# as5600-module.net
KiCad netlist of a schematic drawn in Altium Designer
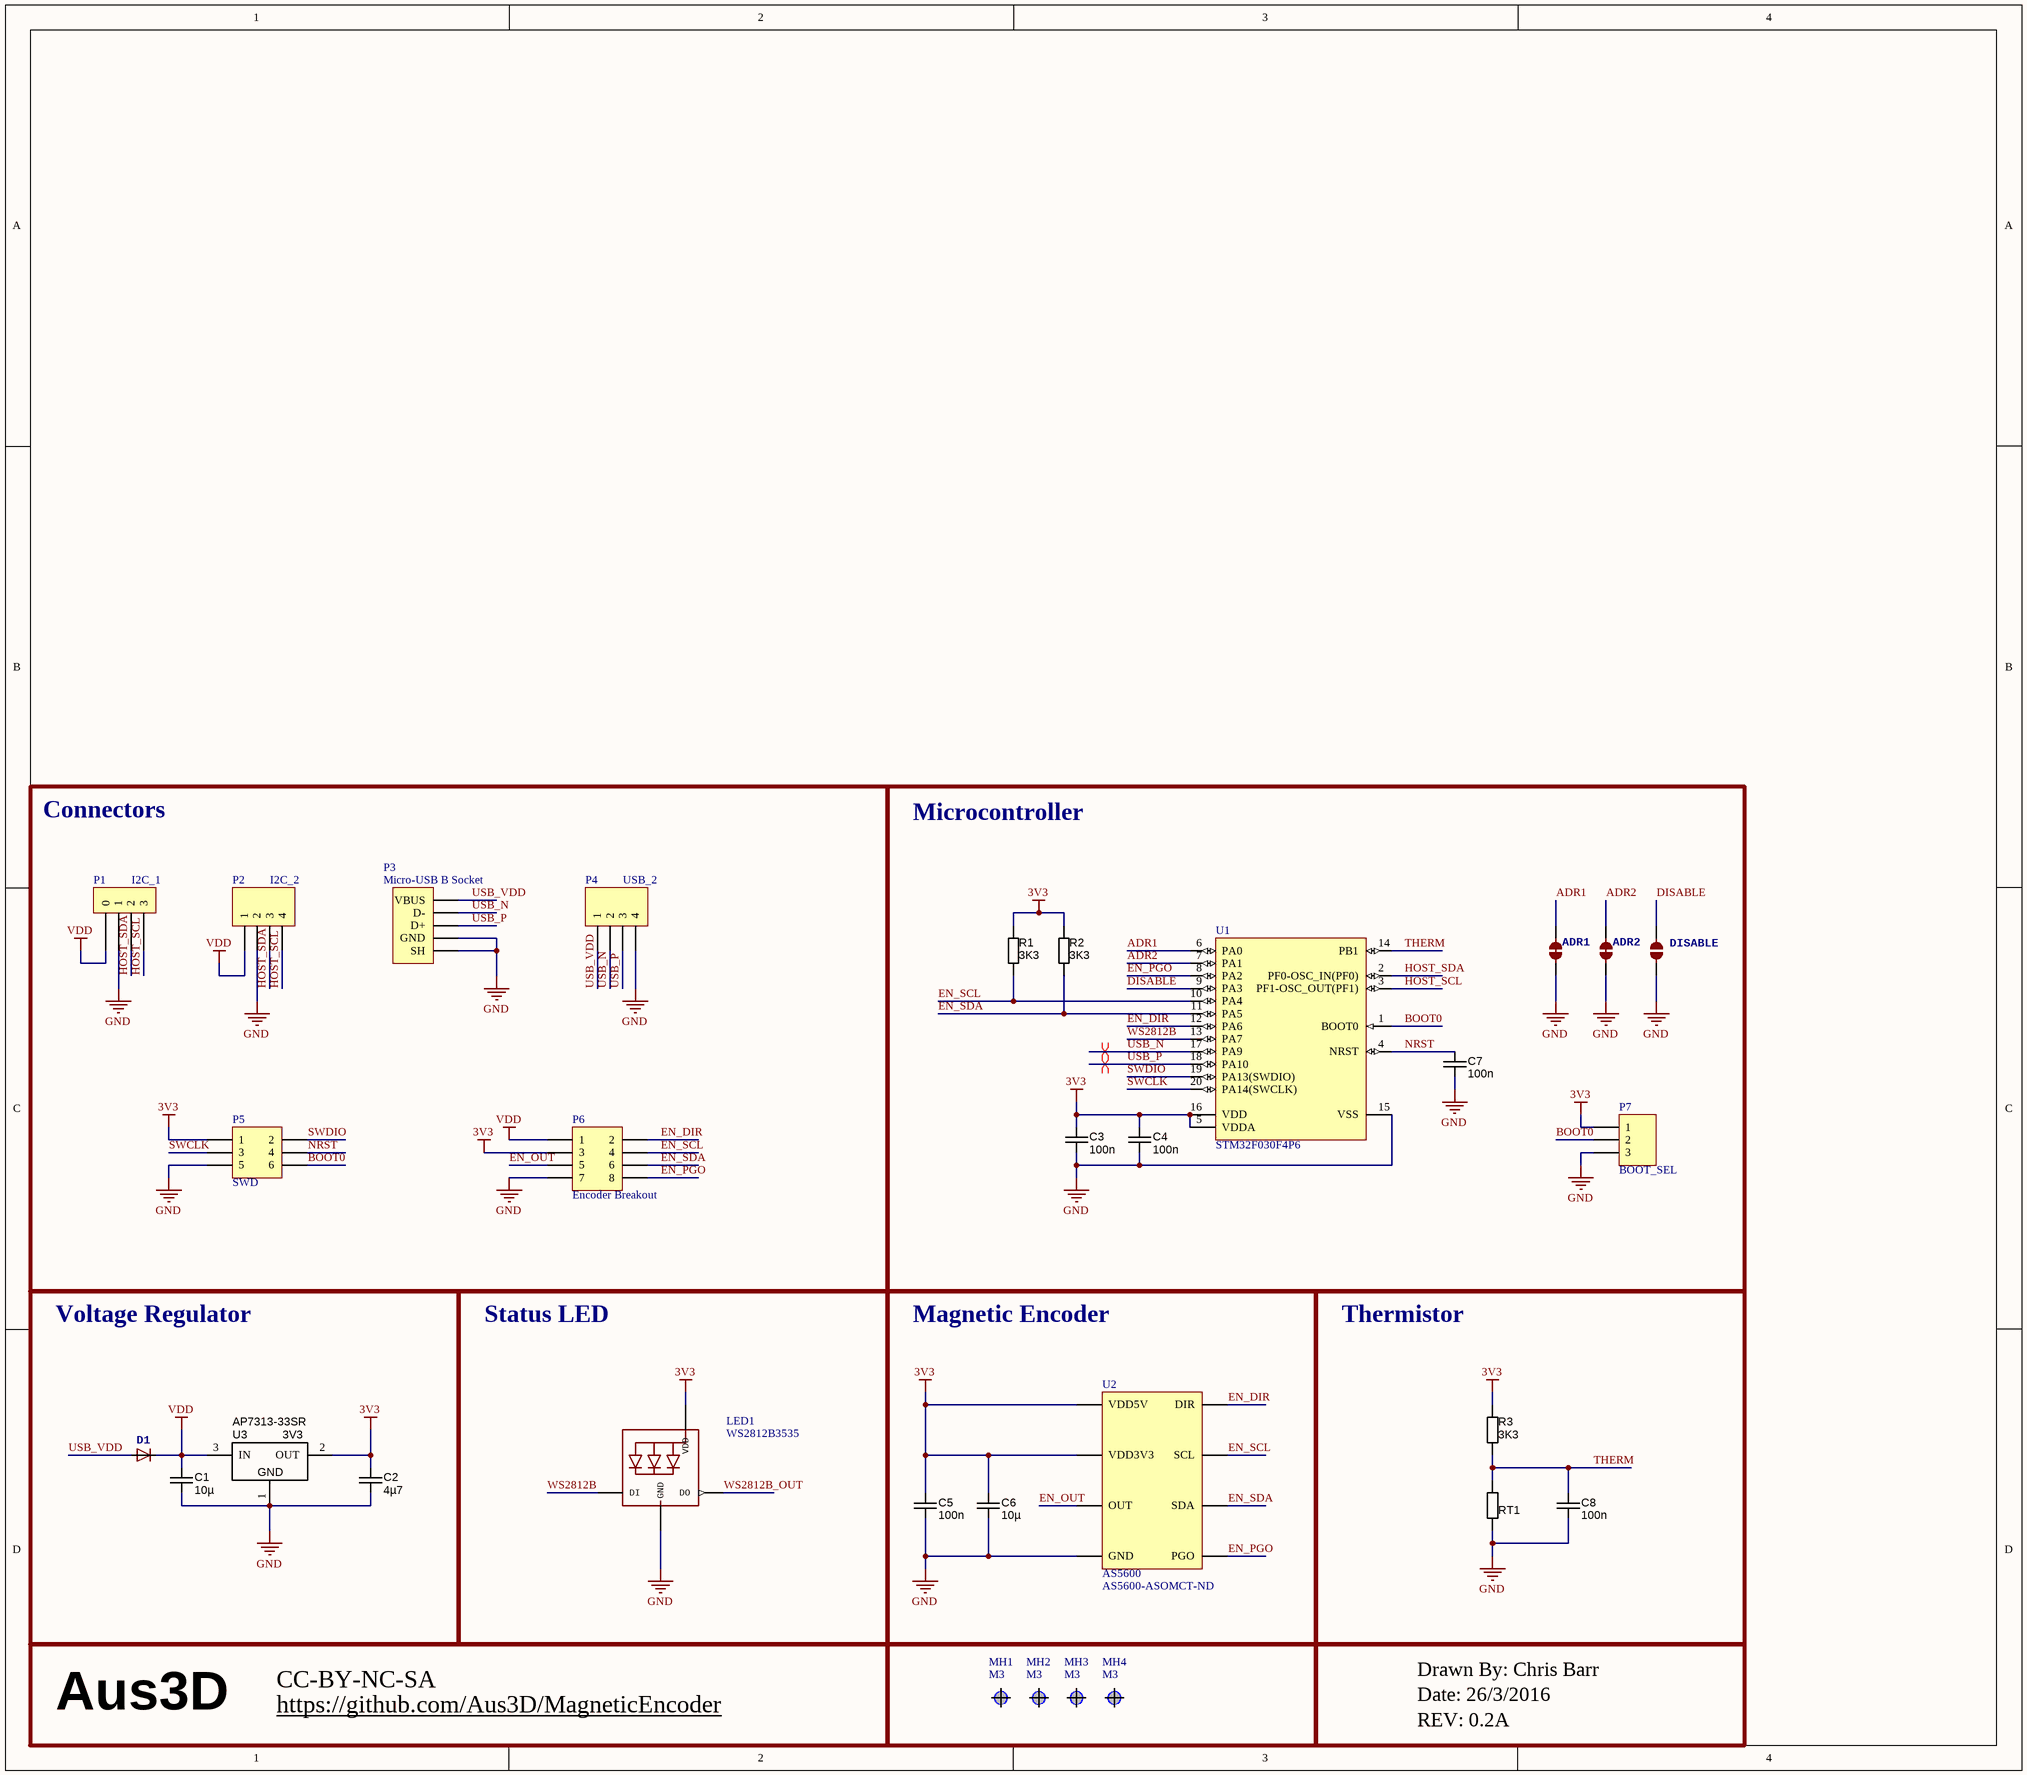
[diagram p0: as5600-module.SchDoc]

(export (version "E")
  (design (tool "Eeschema 10.0.6"))
  (components
    (comp (ref "ADR1")
      (value "JUMPER-PAD-2-NC_BY_TRACE")
      (footprint "PAD-JUMPER-2-NC_BY_TRACE_YES_SILK")
      (libsource (lib "SparkFun-Passives") (part "JUMPER-PAD-2-NC_BY_TRACE"))
    )
    (comp (ref "ADR2")
      (value "JUMPER-PAD-2-NC_BY_TRACE")
      (footprint "PAD-JUMPER-2-NC_BY_TRACE_YES_SILK")
      (libsource (lib "SparkFun-Passives") (part "JUMPER-PAD-2-NC_BY_TRACE"))
    )
    (comp (ref "C1")
      (value "10µ")
      (footprint "CAPC2012X135N")
      (description "Capacitor SMD Cer 10uF 10% 10V X5R 0805")
      (fields (field (name "TOLERANCE") "±10%") (field (name "Comment") "approved sub OK"))
      (libsource (lib "PBL - Capacitors") (part "CAPC_10u_0805_10V"))
    )
    (comp (ref "C2")
      (value "4µ7")
      (footprint "CAPC2012X135N")
      (description "Capacitor SMD Cer 4.7uF 10% 16V X5R 0805")
      (fields (field (name "TOLERANCE") "±10%") (field (name "Comment") "approved sub OK"))
      (libsource (lib "PBL - Capacitors") (part "CAPC_4u7_0805"))
    )
    (comp (ref "C3")
      (value "100n")
      (footprint "CAPC2012X135N")
      (description "Capacitor SMD Cer 100nF 10% 50V X7R 0805")
      (fields (field (name "TOLERANCE") "±10%") (field (name "Comment") "approved sub OK"))
      (libsource (lib "PBL - Capacitors") (part "CAPC_100n_0805_X7R_50V_10%"))
    )
    (comp (ref "C4")
      (value "100n")
      (footprint "CAPC2012X135N")
      (description "Capacitor SMD Cer 100nF 10% 50V X7R 0805")
      (fields (field (name "TOLERANCE") "±10%") (field (name "Comment") "approved sub OK"))
      (libsource (lib "PBL - Capacitors") (part "CAPC_100n_0805_X7R_50V_10%"))
    )
    (comp (ref "C5")
      (value "100n")
      (footprint "CAPC2012X135N")
      (description "Capacitor SMD Cer 100nF 10% 50V X7R 0805")
      (fields (field (name "TOLERANCE") "±10%") (field (name "Comment") "approved sub OK"))
      (libsource (lib "PBL - Capacitors") (part "CAPC_100n_0805_X7R_50V_10%"))
    )
    (comp (ref "C6")
      (value "10µ")
      (footprint "CAPC2012X135N")
      (description "Capacitor SMD Cer 10uF 10% 10V X5R 0805")
      (fields (field (name "TOLERANCE") "±10%") (field (name "Comment") "approved sub OK"))
      (libsource (lib "PBL - Capacitors") (part "CAPC_10u_0805_10V"))
    )
    (comp (ref "C7")
      (value "100n")
      (footprint "CAPC2012X135N")
      (description "Capacitor SMD Cer 100nF 10% 50V X7R 0805")
      (fields (field (name "TOLERANCE") "±10%") (field (name "Comment") "approved sub OK"))
      (libsource (lib "PBL - Capacitors") (part "CAPC_100n_0805_X7R_50V_10%"))
    )
    (comp (ref "C8")
      (value "100n")
      (footprint "CAPC2012X135N")
      (description "Capacitor SMD Cer 100nF 10% 50V X7R 0805")
      (fields (field (name "TOLERANCE") "±10%") (field (name "Comment") "approved sub OK"))
      (libsource (lib "PBL - Capacitors") (part "CAPC_100n_0805_X7R_50V_10%"))
    )
    (comp (ref "D1")
      (value "Diode   SMADIODE - SMA Surface Mount Package  20V 1A Schottky Diode Digikey: 641-1014-6-ND    DO-1N4148 - Through Hole Small Current Diode SOD-123 20V 1 A (.5mV Vf) Schottky Diode - Digikey: MBRX120TPMSCT-ND    SOD-323 10V 570mA (.38mV Vf, 3ns) Schottky Diode - Digikey: ZLLS410CT-ND    SOD-523 30V 30mA Schottky Diode (RB751S-40TE61) - Digikey: RB751S-40TE61CT-ND    SOT23-R/W - SOT23 Package (R = Solder Paste/Reflow Ovens, W = Hand-Soldering)  BAT54Film 40V 300mA - Digikey: 497-7162-1-ND")
      (footprint "SOT23-R")
      (libsource (lib "adafruit") (part "DIODESOT23_REFLOW"))
    )
    (comp (ref "DISABLE")
      (value "JUMPER-PAD-2-NO")
      (footprint "PAD-JUMPER-2-NO_NO_SILK")
      (libsource (lib "SparkFun-Passives") (part "JUMPER-PAD-2-NO"))
    )
    (comp (ref "LED1")
      (value "WS2812B3535")
      (footprint "LED3535")
      (libsource (lib "adafruit") (part "WS2812B3535"))
    )
    (comp (ref "MH1") (value "M3") (footprint "M3-Hole-3") (libsource (lib "Schlib1") (part "Screw Hole")))
    (comp (ref "MH2") (value "M3") (footprint "M3-Hole-3") (libsource (lib "Schlib1") (part "Screw Hole")))
    (comp (ref "MH3") (value "M3") (footprint "M3-Hole-3") (libsource (lib "Schlib1") (part "Screw Hole")))
    (comp (ref "MH4") (value "M3") (footprint "M3-Hole-3") (libsource (lib "Schlib1") (part "Screw Hole")))
    (comp (ref "P1")
      (value "I2C_1")
      (footprint "SM04B-SRSS-TB")
      (libsource (lib "Schlib1") (part "SM04B-SRSS-TB"))
    )
    (comp (ref "P2")
      (value "I2C_2")
      (footprint "HDR1X4")
      (description "Header, 4-Pin")
      (fields (field (name "PUBLISHER") "Altium Limited"))
      (libsource (lib "Miscellaneous Connectors") (part "Header 4"))
    )
    (comp (ref "P3")
      (value "Micro-USB B Socket")
      (footprint "Micro-USB B Molex 105017-0001")
      (libsource (lib "Schlib1") (part "Micro-USB B Socket"))
    )
    (comp (ref "P4")
      (value "USB_2")
      (footprint "HDR1X4")
      (description "Header, 4-Pin")
      (fields (field (name "PUBLISHER") "Altium Limited"))
      (libsource (lib "Miscellaneous Connectors") (part "Header 4"))
    )
    (comp (ref "P5")
      (value "SWD")
      (footprint "HDR2X3")
      (description "Header, 3-Pin, Dual row")
      (fields (field (name "PUBLISHER") "Altium Limited"))
      (libsource (lib "Miscellaneous Connectors") (part "Header 3X2"))
    )
    (comp (ref "P6")
      (value "Encoder Breakout")
      (footprint "HDR2X4")
      (description "Header, 4-Pin, Dual row")
      (fields (field (name "PUBLISHER") "Altium Limited"))
      (libsource (lib "Miscellaneous Connectors") (part "Header 4X2"))
    )
    (comp (ref "P7")
      (value "BOOT_SEL")
      (footprint "HDR1X3")
      (description "Header, 3-Pin")
      (fields (field (name "PUBLISHER") "Altium Limited"))
      (libsource (lib "Miscellaneous Connectors") (part "Header 3"))
    )
    (comp (ref "R1")
      (value "3K3")
      (footprint "RESC2012X70N")
      (description "Resistor SMD chip 3.3k Ohm 0.125W 1% 0805")
      (fields (field (name "TOLERANCE") "±1%") (field (name "Comment") "Thick Film"))
      (libsource (lib "PBL - Resistors") (part "RES_3K3_0805_1%"))
    )
    (comp (ref "R2")
      (value "3K3")
      (footprint "RESC2012X70N")
      (description "Resistor SMD chip 3.3k Ohm 0.125W 1% 0805")
      (fields (field (name "TOLERANCE") "±1%") (field (name "Comment") "Thick Film"))
      (libsource (lib "PBL - Resistors") (part "RES_3K3_0805_1%"))
    )
    (comp (ref "R3")
      (value "3K3")
      (footprint "RESC2012X70N")
      (description "Resistor SMD chip 3.3k Ohm 0.125W 1% 0805")
      (fields (field (name "TOLERANCE") "±1%") (field (name "Comment") "Thick Film"))
      (libsource (lib "PBL - Resistors") (part "RES_3K3_0805_1%"))
    )
    (comp (ref "RT1")
      (value "RES_EMPTY_0805")
      (footprint "RESC2012X70N")
      (description "Resistor, 0805 SMD, Empty footprint")
      (libsource (lib "PBL - Resistors") (part "RES_EMPTY_0805"))
    )
    (comp (ref "U1")
      (value "STM32F030F4P6")
      (footprint "STM-TSSOP20_N")
      (libsource (lib "STMicroelectronics STM32 F0") (part "STM32F030F4P6"))
    )
    (comp (ref "U2")
      (value "AS5600")
      (footprint "AS5600 - SOIC127P600X175-8M")
      (fields (field (name "SUPPLIER PART NUMBER 1") "AS5600-ASOMCT-ND"))
      (libsource (lib "Schlib1") (part "AMS AS5600"))
    )
    (comp (ref "U3")
      (value "AP7313-33SR")
      (footprint "SOT23-3")
      (description "Voltage Regulator 3.3V LDO SOT23R-3 SMD")
      (fields (field (name "TOLERANCE") "±2%") (field (name "ALTIUM_VALUE") "3V3"))
      (libsource (lib "PBL - Regulators") (part "VREG_3V3_AP7313-33SR"))
    )
  )
  (nets
    (net (code "1") (name "/ADR1") (class "Default")
      (node (ref "ADR1") (pin "2") (pinfunction "2_2") (pintype "passive"))
      (node (ref "U1") (pin "6") (pinfunction "PA0_6") (pintype "bidirectional"))
    )
    (net (code "2") (name "/ADR2") (class "Default")
      (node (ref "ADR2") (pin "2") (pinfunction "2_2") (pintype "passive"))
      (node (ref "U1") (pin "7") (pinfunction "PA1_7") (pintype "bidirectional"))
    )
    (net (code "3") (name "/BOOT0") (class "Default")
      (node (ref "P5") (pin "6") (pinfunction "6_6") (pintype "passive"))
      (node (ref "P7") (pin "2") (pinfunction "2_2") (pintype "passive"))
      (node (ref "U1") (pin "1") (pinfunction "BOOT0_1") (pintype "input"))
    )
    (net (code "4") (name "/DISABLE") (class "Default")
      (node (ref "DISABLE") (pin "1") (pinfunction "1_1") (pintype "passive"))
      (node (ref "U1") (pin "9") (pinfunction "PA3_9") (pintype "bidirectional"))
    )
    (net (code "5") (name "/EN_DIR") (class "Default")
      (node (ref "P6") (pin "2") (pinfunction "2_2") (pintype "passive"))
      (node (ref "U1") (pin "12") (pinfunction "PA6_12") (pintype "bidirectional"))
      (node (ref "U2") (pin "8") (pinfunction "DIR_8") (pintype "passive"))
    )
    (net (code "6") (name "/EN_OUT") (class "Default")
      (node (ref "P6") (pin "5") (pinfunction "5_5") (pintype "passive"))
      (node (ref "U2") (pin "3") (pinfunction "OUT_3") (pintype "passive"))
    )
    (net (code "7") (name "/EN_PGO") (class "Default")
      (node (ref "P6") (pin "8") (pinfunction "8_8") (pintype "passive"))
      (node (ref "U1") (pin "8") (pinfunction "PA2_8") (pintype "bidirectional"))
      (node (ref "U2") (pin "5") (pinfunction "PGO_5") (pintype "passive"))
    )
    (net (code "8") (name "/EN_SCL") (class "Default")
      (node (ref "P6") (pin "4") (pinfunction "4_4") (pintype "passive"))
      (node (ref "R1") (pin "2") (pinfunction "2_2") (pintype "passive"))
      (node (ref "U1") (pin "10") (pinfunction "PA4_10") (pintype "bidirectional"))
      (node (ref "U2") (pin "7") (pinfunction "SCL_7") (pintype "passive"))
    )
    (net (code "9") (name "/EN_SDA") (class "Default")
      (node (ref "P6") (pin "6") (pinfunction "6_6") (pintype "passive"))
      (node (ref "R2") (pin "2") (pinfunction "2_2") (pintype "passive"))
      (node (ref "U1") (pin "11") (pinfunction "PA5_11") (pintype "bidirectional"))
      (node (ref "U2") (pin "6") (pinfunction "SDA_6") (pintype "passive"))
    )
    (net (code "10") (name "/HOST_SCL") (class "Default")
      (node (ref "P1") (pin "3") (pinfunction "3_3") (pintype "passive"))
      (node (ref "P2") (pin "4") (pinfunction "4_4") (pintype "passive"))
      (node (ref "U1") (pin "3") (pinfunction "PF1-OSC_OUT(PF1)_3") (pintype "bidirectional"))
    )
    (net (code "11") (name "/HOST_SDA") (class "Default")
      (node (ref "P1") (pin "2") (pinfunction "2_2") (pintype "passive"))
      (node (ref "P2") (pin "3") (pinfunction "3_3") (pintype "passive"))
      (node (ref "U1") (pin "2") (pinfunction "PF0-OSC_IN(PF0)_2") (pintype "bidirectional"))
    )
    (net (code "12") (name "/NRST") (class "Default")
      (node (ref "C7") (pin "1") (pintype "passive"))
      (node (ref "P5") (pin "4") (pinfunction "4_4") (pintype "passive"))
      (node (ref "U1") (pin "4") (pinfunction "NRST_4") (pintype "bidirectional"))
    )
    (net (code "13") (name "/SWCLK") (class "Default")
      (node (ref "P5") (pin "3") (pinfunction "3_3") (pintype "passive"))
      (node (ref "U1") (pin "20") (pinfunction "PA14(SWCLK)_20") (pintype "bidirectional"))
    )
    (net (code "14") (name "/SWDIO") (class "Default")
      (node (ref "P5") (pin "2") (pinfunction "2_2") (pintype "passive"))
      (node (ref "U1") (pin "19") (pinfunction "PA13(SWDIO)_19") (pintype "bidirectional"))
    )
    (net (code "15") (name "/THERM") (class "Default")
      (node (ref "C8") (pin "1") (pintype "passive"))
      (node (ref "R3") (pin "2") (pinfunction "2_2") (pintype "passive"))
      (node (ref "RT1") (pin "2") (pinfunction "2_2") (pintype "passive"))
      (node (ref "U1") (pin "14") (pinfunction "PB1_14") (pintype "bidirectional"))
    )
    (net (code "16") (name "/USB_N") (class "Default")
      (node (ref "P3") (pin "D-") (pinfunction "D-_D-") (pintype "passive"))
      (node (ref "P4") (pin "2") (pinfunction "2_2") (pintype "passive"))
      (node (ref "U1") (pin "17") (pinfunction "PA9_17") (pintype "bidirectional"))
    )
    (net (code "17") (name "/USB_P") (class "Default")
      (node (ref "P3") (pin "D+") (pinfunction "D+_D+") (pintype "passive"))
      (node (ref "P4") (pin "3") (pinfunction "3_3") (pintype "passive"))
      (node (ref "U1") (pin "18") (pinfunction "PA10_18") (pintype "bidirectional"))
    )
    (net (code "18") (name "/USB_VDD") (class "Default")
      (node (ref "D1") (pin "1") (pinfunction "A_1") (pintype "passive"))
      (node (ref "P3") (pin "VBUS") (pinfunction "VBUS_VBUS") (pintype "passive"))
      (node (ref "P4") (pin "1") (pinfunction "1_1") (pintype "passive"))
    )
    (net (code "19") (name "/WS2812B") (class "Default")
      (node (ref "LED1") (pin "1") (pinfunction "DI_1") (pintype "passive"))
      (node (ref "U1") (pin "13") (pinfunction "PA7_13") (pintype "bidirectional"))
    )
    (net (code "20") (name "/WS2812B_OUT") (class "Default")
      (node (ref "LED1") (pin "3") (pinfunction "DO_3") (pintype "output"))
    )
    (net (code "21") (name "3V3") (class "Default")
      (node (ref "C2") (pin "1") (pintype "passive"))
      (node (ref "C3") (pin "1") (pintype "passive"))
      (node (ref "C4") (pin "1") (pintype "passive"))
      (node (ref "C5") (pin "1") (pintype "passive"))
      (node (ref "C6") (pin "1") (pintype "passive"))
      (node (ref "LED1") (pin "2") (pinfunction "VDD_2") (pintype "power_in"))
      (node (ref "P5") (pin "1") (pinfunction "1_1") (pintype "passive"))
      (node (ref "P6") (pin "3") (pinfunction "3_3") (pintype "passive"))
      (node (ref "P7") (pin "1") (pinfunction "1_1") (pintype "passive"))
      (node (ref "R1") (pin "1") (pinfunction "1_1") (pintype "passive"))
      (node (ref "R2") (pin "1") (pinfunction "1_1") (pintype "passive"))
      (node (ref "R3") (pin "1") (pinfunction "1_1") (pintype "passive"))
      (node (ref "U1") (pin "16") (pinfunction "VDD_16") (pintype "power_in"))
      (node (ref "U1") (pin "5") (pinfunction "VDDA_5") (pintype "power_in"))
      (node (ref "U2") (pin "1") (pinfunction "VDD5V_1") (pintype "passive"))
      (node (ref "U2") (pin "2") (pinfunction "VDD3V3_2") (pintype "passive"))
      (node (ref "U3") (pin "2") (pinfunction "OUT_2") (pintype "power_in"))
    )
    (net (code "22") (name "GND") (class "Default")
      (node (ref "ADR1") (pin "1") (pinfunction "1_1") (pintype "passive"))
      (node (ref "ADR2") (pin "1") (pinfunction "1_1") (pintype "passive"))
      (node (ref "C1") (pin "2") (pintype "passive"))
      (node (ref "C2") (pin "2") (pintype "passive"))
      (node (ref "C3") (pin "2") (pintype "passive"))
      (node (ref "C4") (pin "2") (pintype "passive"))
      (node (ref "C5") (pin "2") (pintype "passive"))
      (node (ref "C6") (pin "2") (pintype "passive"))
      (node (ref "C7") (pin "2") (pintype "passive"))
      (node (ref "C8") (pin "2") (pintype "passive"))
      (node (ref "DISABLE") (pin "2") (pinfunction "2_2") (pintype "passive"))
      (node (ref "LED1") (pin "4") (pinfunction "GND_4") (pintype "power_in"))
      (node (ref "P1") (pin "1") (pinfunction "1_1") (pintype "passive"))
      (node (ref "P2") (pin "2") (pinfunction "2_2") (pintype "passive"))
      (node (ref "P3") (pin "GND") (pinfunction "GND_GND") (pintype "passive"))
      (node (ref "P3") (pin "SHIELD") (pinfunction "SH_SHIELD") (pintype "passive"))
      (node (ref "P4") (pin "4") (pinfunction "4_4") (pintype "passive"))
      (node (ref "P5") (pin "5") (pinfunction "5_5") (pintype "passive"))
      (node (ref "P6") (pin "7") (pinfunction "7_7") (pintype "passive"))
      (node (ref "P7") (pin "3") (pinfunction "3_3") (pintype "passive"))
      (node (ref "RT1") (pin "1") (pinfunction "1_1") (pintype "passive"))
      (node (ref "U1") (pin "15") (pinfunction "VSS_15") (pintype "power_in"))
      (node (ref "U2") (pin "4") (pinfunction "GND_4") (pintype "passive"))
      (node (ref "U3") (pin "1") (pinfunction "GND_1") (pintype "power_in"))
    )
    (net (code "23") (name "VDD") (class "Default")
      (node (ref "C1") (pin "1") (pintype "passive"))
      (node (ref "D1") (pin "3") (pinfunction "C_3") (pintype "passive"))
      (node (ref "P1") (pin "0") (pinfunction "0_0") (pintype "passive"))
      (node (ref "P2") (pin "1") (pinfunction "1_1") (pintype "passive"))
      (node (ref "P6") (pin "1") (pinfunction "1_1") (pintype "passive"))
      (node (ref "U3") (pin "3") (pinfunction "IN_3") (pintype "power_in"))
    )
    (net (code "24") (name "unconnected-(MH1-0-PadM3)") (class "Default")
      (node (ref "MH1") (pin "M3") (pinfunction "0_M3") (pintype "passive"))
    )
    (net (code "25") (name "unconnected-(MH2-0-PadM3)") (class "Default")
      (node (ref "MH2") (pin "M3") (pinfunction "0_M3") (pintype "passive"))
    )
    (net (code "26") (name "unconnected-(MH3-0-PadM3)") (class "Default")
      (node (ref "MH3") (pin "M3") (pinfunction "0_M3") (pintype "passive"))
    )
    (net (code "27") (name "unconnected-(MH4-0-PadM3)") (class "Default")
      (node (ref "MH4") (pin "M3") (pinfunction "0_M3") (pintype "passive"))
    )
  )
)
